# StepperSynth2_4_Interface.net
KiCad netlist of a schematic drawn in EAGLE
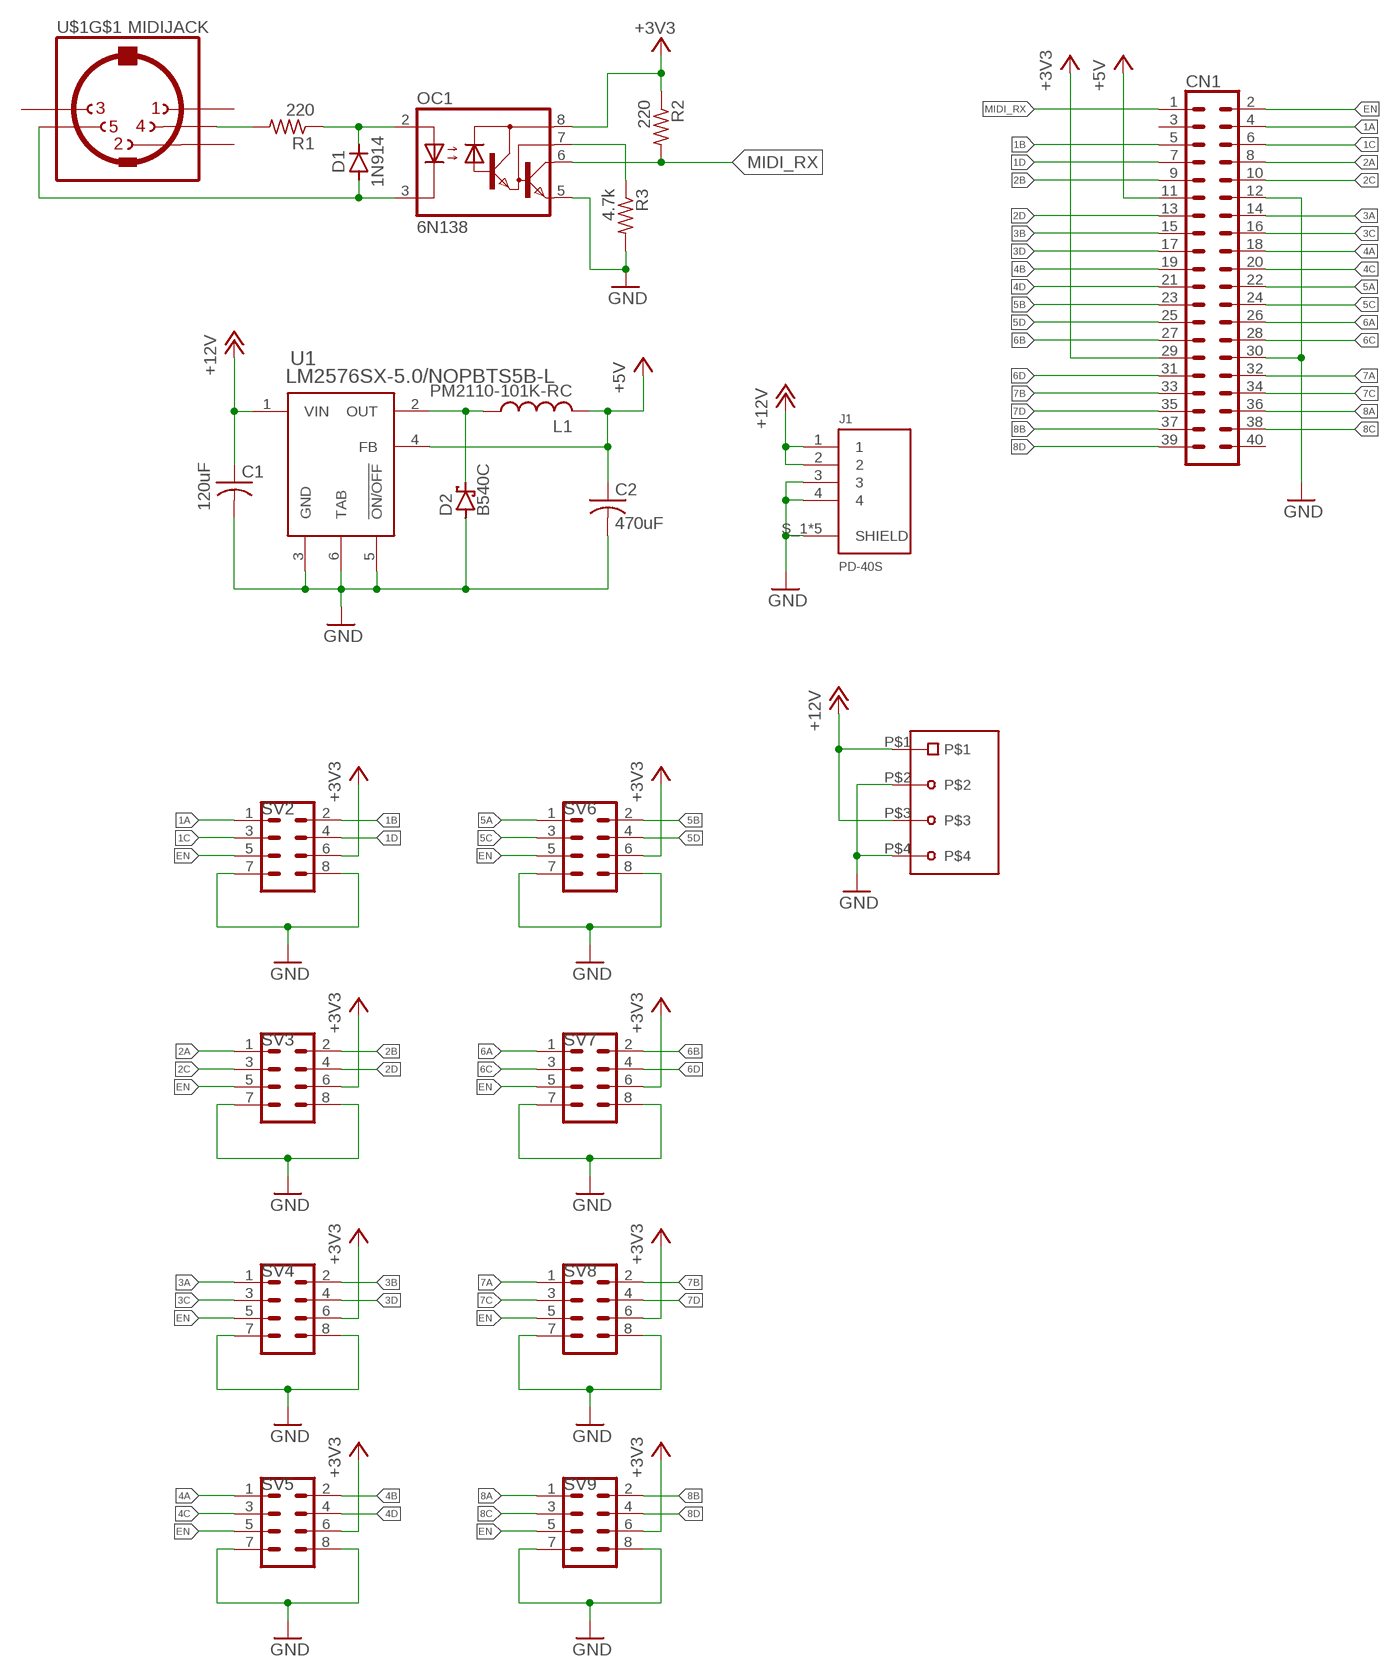
[diagram p0: schematic, sheet 1]

(export (version "E")
  (design (tool "Eeschema 10.0.6"))
  (components
    (comp (ref "C1")
      (value "120uF")
      (footprint "eagle-import:PCAP_SVP_C6-L")
      (fields (field (name "MANUFACTURER_PART_NUMBER") "20SVPF120M"))
      (libsource (lib "eagle-import") (part "20SVPF120MPCAP_SVP_C6-L"))
    )
    (comp (ref "C2")
      (value "470uF")
      (footprint "eagle-import:U2-P-L")
      (fields (field (name "MANUFACTURER_PART_NUMBER") "UUD1A471MNL1GS"))
      (libsource (lib "eagle-import") (part "UUD1A471MNL1GSU2-P-L"))
    )
    (comp (ref "CN1")
      (value "CONN_20X2_LOCK")
      (footprint "eagle-import:1X20_LOCK")
      (libsource (lib "eagle-import") (part "CONN_20X2_LOCK"))
    )
    (comp (ref "CN2")
      (value "SCREW_TERMINAL_4POS_5MM")
      (footprint "eagle-import:4_POS-SCREW_TERM")
      (libsource (lib "eagle-import") (part "SCREW_TERMINAL_4POS_5MM"))
    )
    (comp (ref "D1")
      (value "1N914")
      (footprint "eagle-import:DO35-7")
      (libsource (lib "eagle-import") (part "1N914"))
    )
    (comp (ref "D2")
      (value "B540C")
      (footprint "eagle-import:SMC")
      (libsource (lib "eagle-import") (part "SCHOTTKY-DIODESMC"))
    )
    (comp (ref "J1")
      (value "PD-40S")
      (footprint "eagle-import:CUI_PD-40S")
      (fields (field (name "DIGI-KEY_PART_NUMBER") "CP-7240-ND") (field (name "MF") "CUI Inc."))
      (libsource (lib "eagle-import") (part "PD-40S"))
    )
    (comp (ref "L1")
      (value "PM2110-101K-RC")
      (footprint "eagle-import:IND_PM2110")
      (fields (field (name "MANUFACTURER_PART_NUMBER") "PM2110101KRC"))
      (libsource (lib "eagle-import") (part "PM2110-101K-RC"))
    )
    (comp (ref "OC1")
      (value "6N138")
      (footprint "eagle-import:DIL08")
      (fields (field (name "MF") "VISHAY/TELEFUNKEN"))
      (libsource (lib "eagle-import") (part "6N138"))
    )
    (comp (ref "R1")
      (value "220")
      (footprint "eagle-import:0204_7")
      (libsource (lib "eagle-import") (part "R-US_0204/7"))
    )
    (comp (ref "R2")
      (value "220")
      (footprint "eagle-import:0204_7")
      (libsource (lib "eagle-import") (part "R-US_0204/7"))
    )
    (comp (ref "R3")
      (value "4.7k")
      (footprint "eagle-import:0204_7")
      (libsource (lib "eagle-import") (part "R-US_0204/7"))
    )
    (comp (ref "SV2")
      (value "CONN_4X2_LOCK")
      (footprint "eagle-import:1X04_LOCK")
      (libsource (lib "eagle-import") (part "CONN_4X2_LOCK"))
    )
    (comp (ref "SV3")
      (value "CONN_4X2_LOCK")
      (footprint "eagle-import:1X04_LOCK")
      (libsource (lib "eagle-import") (part "CONN_4X2_LOCK"))
    )
    (comp (ref "SV4")
      (value "CONN_4X2_LOCK")
      (footprint "eagle-import:1X04_LOCK")
      (libsource (lib "eagle-import") (part "CONN_4X2_LOCK"))
    )
    (comp (ref "SV5")
      (value "CONN_4X2_LOCK")
      (footprint "eagle-import:1X04_LOCK")
      (libsource (lib "eagle-import") (part "CONN_4X2_LOCK"))
    )
    (comp (ref "SV6")
      (value "CONN_4X2_LOCK")
      (footprint "eagle-import:1X04_LOCK")
      (libsource (lib "eagle-import") (part "CONN_4X2_LOCK"))
    )
    (comp (ref "SV7")
      (value "CONN_4X2_LOCK")
      (footprint "eagle-import:1X04_LOCK")
      (libsource (lib "eagle-import") (part "CONN_4X2_LOCK"))
    )
    (comp (ref "SV8")
      (value "CONN_4X2_LOCK")
      (footprint "eagle-import:1X04_LOCK")
      (libsource (lib "eagle-import") (part "CONN_4X2_LOCK"))
    )
    (comp (ref "SV9")
      (value "CONN_4X2_LOCK")
      (footprint "eagle-import:1X04_LOCK")
      (libsource (lib "eagle-import") (part "CONN_4X2_LOCK"))
    )
    (comp (ref "U$1")
      (value "MIDIJACK")
      (footprint "eagle-import:CP-2350")
      (libsource (lib "eagle-import") (part "MIDIJACK"))
    )
    (comp (ref "U1")
      (value "LM2576SX-5.0/NOPBTS5B-L")
      (footprint "eagle-import:TS5B-L")
      (fields (field (name "MANUFACTURER_PART_NUMBER") "LM2576SX5.0NOPB"))
      (libsource (lib "eagle-import") (part "LM2576SX-5.0/NOPBTS5B-L"))
    )
  )
  (nets
    (net (code "1") (name "+3V3") (class "Default")
      (node (ref "CN1") (pin "29") (pinfunction "29_29") (pintype "passive"))
      (node (ref "OC1") (pin "8") (pinfunction "VCC_8") (pintype "passive"))
      (node (ref "R2") (pin "1") (pinfunction "1_1") (pintype "passive"))
      (node (ref "SV2") (pin "6") (pinfunction "6_6") (pintype "passive"))
      (node (ref "SV3") (pin "6") (pinfunction "6_6") (pintype "passive"))
      (node (ref "SV4") (pin "6") (pinfunction "6_6") (pintype "passive"))
      (node (ref "SV5") (pin "6") (pinfunction "6_6") (pintype "passive"))
      (node (ref "SV6") (pin "6") (pinfunction "6_6") (pintype "passive"))
      (node (ref "SV7") (pin "6") (pinfunction "6_6") (pintype "passive"))
      (node (ref "SV8") (pin "6") (pinfunction "6_6") (pintype "passive"))
      (node (ref "SV9") (pin "6") (pinfunction "6_6") (pintype "passive"))
    )
    (net (code "2") (name "+5V") (class "Default")
      (node (ref "C2") (pin "1") (pinfunction "+_1") (pintype "passive"))
      (node (ref "CN1") (pin "11") (pinfunction "11_11") (pintype "passive"))
      (node (ref "L1") (pin "2") (pinfunction "2_2") (pintype "passive"))
      (node (ref "U1") (pin "4") (pinfunction "FB_4") (pintype "input"))
    )
    (net (code "3") (name "+12V") (class "Default")
      (node (ref "C1") (pin "1") (pinfunction "+_1") (pintype "passive"))
      (node (ref "CN2") (pin "P$1") (pinfunction "P$1_P$1") (pintype "bidirectional"))
      (node (ref "CN2") (pin "P$3") (pinfunction "P$3_P$3") (pintype "bidirectional"))
      (node (ref "J1") (pin "1") (pinfunction "1_1") (pintype "passive"))
      (node (ref "J1") (pin "2") (pinfunction "2_2") (pintype "passive"))
      (node (ref "U1") (pin "1") (pinfunction "VIN_1") (pintype "power_in"))
    )
    (net (code "4") (name "1A") (class "Default")
      (node (ref "CN1") (pin "4") (pinfunction "4_4") (pintype "passive"))
      (node (ref "SV2") (pin "1") (pinfunction "1_1") (pintype "passive"))
    )
    (net (code "5") (name "1B") (class "Default")
      (node (ref "CN1") (pin "5") (pinfunction "5_5") (pintype "passive"))
      (node (ref "SV2") (pin "2") (pinfunction "2_2") (pintype "passive"))
    )
    (net (code "6") (name "1C") (class "Default")
      (node (ref "CN1") (pin "6") (pinfunction "6_6") (pintype "passive"))
      (node (ref "SV2") (pin "3") (pinfunction "3_3") (pintype "passive"))
    )
    (net (code "7") (name "1D") (class "Default")
      (node (ref "CN1") (pin "7") (pinfunction "7_7") (pintype "passive"))
      (node (ref "SV2") (pin "4") (pinfunction "4_4") (pintype "passive"))
    )
    (net (code "8") (name "2A") (class "Default")
      (node (ref "CN1") (pin "8") (pinfunction "8_8") (pintype "passive"))
      (node (ref "SV3") (pin "1") (pinfunction "1_1") (pintype "passive"))
    )
    (net (code "9") (name "2B") (class "Default")
      (node (ref "CN1") (pin "9") (pinfunction "9_9") (pintype "passive"))
      (node (ref "SV3") (pin "2") (pinfunction "2_2") (pintype "passive"))
    )
    (net (code "10") (name "2C") (class "Default")
      (node (ref "CN1") (pin "10") (pinfunction "10_10") (pintype "passive"))
      (node (ref "SV3") (pin "3") (pinfunction "3_3") (pintype "passive"))
    )
    (net (code "11") (name "2D") (class "Default")
      (node (ref "CN1") (pin "13") (pinfunction "13_13") (pintype "passive"))
      (node (ref "SV3") (pin "4") (pinfunction "4_4") (pintype "passive"))
    )
    (net (code "12") (name "3A") (class "Default")
      (node (ref "CN1") (pin "14") (pinfunction "14_14") (pintype "passive"))
      (node (ref "SV4") (pin "1") (pinfunction "1_1") (pintype "passive"))
    )
    (net (code "13") (name "3B") (class "Default")
      (node (ref "CN1") (pin "15") (pinfunction "15_15") (pintype "passive"))
      (node (ref "SV4") (pin "2") (pinfunction "2_2") (pintype "passive"))
    )
    (net (code "14") (name "3C") (class "Default")
      (node (ref "CN1") (pin "16") (pinfunction "16_16") (pintype "passive"))
      (node (ref "SV4") (pin "3") (pinfunction "3_3") (pintype "passive"))
    )
    (net (code "15") (name "3D") (class "Default")
      (node (ref "CN1") (pin "17") (pinfunction "17_17") (pintype "passive"))
      (node (ref "SV4") (pin "4") (pinfunction "4_4") (pintype "passive"))
    )
    (net (code "16") (name "4A") (class "Default")
      (node (ref "CN1") (pin "18") (pinfunction "18_18") (pintype "passive"))
      (node (ref "SV5") (pin "1") (pinfunction "1_1") (pintype "passive"))
    )
    (net (code "17") (name "4B") (class "Default")
      (node (ref "CN1") (pin "19") (pinfunction "19_19") (pintype "passive"))
      (node (ref "SV5") (pin "2") (pinfunction "2_2") (pintype "passive"))
    )
    (net (code "18") (name "4C") (class "Default")
      (node (ref "CN1") (pin "20") (pinfunction "20_20") (pintype "passive"))
      (node (ref "SV5") (pin "3") (pinfunction "3_3") (pintype "passive"))
    )
    (net (code "19") (name "4D") (class "Default")
      (node (ref "CN1") (pin "21") (pinfunction "21_21") (pintype "passive"))
      (node (ref "SV5") (pin "4") (pinfunction "4_4") (pintype "passive"))
    )
    (net (code "20") (name "5A") (class "Default")
      (node (ref "CN1") (pin "22") (pinfunction "22_22") (pintype "passive"))
      (node (ref "SV6") (pin "1") (pinfunction "1_1") (pintype "passive"))
    )
    (net (code "21") (name "5B") (class "Default")
      (node (ref "CN1") (pin "23") (pinfunction "23_23") (pintype "passive"))
      (node (ref "SV6") (pin "2") (pinfunction "2_2") (pintype "passive"))
    )
    (net (code "22") (name "5C") (class "Default")
      (node (ref "CN1") (pin "24") (pinfunction "24_24") (pintype "passive"))
      (node (ref "SV6") (pin "3") (pinfunction "3_3") (pintype "passive"))
    )
    (net (code "23") (name "5D") (class "Default")
      (node (ref "CN1") (pin "25") (pinfunction "25_25") (pintype "passive"))
      (node (ref "SV6") (pin "4") (pinfunction "4_4") (pintype "passive"))
    )
    (net (code "24") (name "6A") (class "Default")
      (node (ref "CN1") (pin "26") (pinfunction "26_26") (pintype "passive"))
      (node (ref "SV7") (pin "1") (pinfunction "1_1") (pintype "passive"))
    )
    (net (code "25") (name "6B") (class "Default")
      (node (ref "CN1") (pin "27") (pinfunction "27_27") (pintype "passive"))
      (node (ref "SV7") (pin "2") (pinfunction "2_2") (pintype "passive"))
    )
    (net (code "26") (name "6C") (class "Default")
      (node (ref "CN1") (pin "28") (pinfunction "28_28") (pintype "passive"))
      (node (ref "SV7") (pin "3") (pinfunction "3_3") (pintype "passive"))
    )
    (net (code "27") (name "6D") (class "Default")
      (node (ref "CN1") (pin "31") (pinfunction "31_31") (pintype "passive"))
      (node (ref "SV7") (pin "4") (pinfunction "4_4") (pintype "passive"))
    )
    (net (code "28") (name "7A") (class "Default")
      (node (ref "CN1") (pin "32") (pinfunction "32_32") (pintype "passive"))
      (node (ref "SV8") (pin "1") (pinfunction "1_1") (pintype "passive"))
    )
    (net (code "29") (name "7B") (class "Default")
      (node (ref "CN1") (pin "33") (pinfunction "33_33") (pintype "passive"))
      (node (ref "SV8") (pin "2") (pinfunction "2_2") (pintype "passive"))
    )
    (net (code "30") (name "7C") (class "Default")
      (node (ref "CN1") (pin "34") (pinfunction "34_34") (pintype "passive"))
      (node (ref "SV8") (pin "3") (pinfunction "3_3") (pintype "passive"))
    )
    (net (code "31") (name "7D") (class "Default")
      (node (ref "CN1") (pin "35") (pinfunction "35_35") (pintype "passive"))
      (node (ref "SV8") (pin "4") (pinfunction "4_4") (pintype "passive"))
    )
    (net (code "32") (name "8A") (class "Default")
      (node (ref "CN1") (pin "36") (pinfunction "36_36") (pintype "passive"))
      (node (ref "SV9") (pin "1") (pinfunction "1_1") (pintype "passive"))
    )
    (net (code "33") (name "8B") (class "Default")
      (node (ref "CN1") (pin "37") (pinfunction "37_37") (pintype "passive"))
      (node (ref "SV9") (pin "2") (pinfunction "2_2") (pintype "passive"))
    )
    (net (code "34") (name "8C") (class "Default")
      (node (ref "CN1") (pin "38") (pinfunction "38_38") (pintype "passive"))
      (node (ref "SV9") (pin "3") (pinfunction "3_3") (pintype "passive"))
    )
    (net (code "35") (name "8D") (class "Default")
      (node (ref "CN1") (pin "39") (pinfunction "39_39") (pintype "passive"))
      (node (ref "SV9") (pin "4") (pinfunction "4_4") (pintype "passive"))
    )
    (net (code "36") (name "EN") (class "Default")
      (node (ref "CN1") (pin "2") (pinfunction "2_2") (pintype "passive"))
      (node (ref "SV2") (pin "5") (pinfunction "5_5") (pintype "passive"))
      (node (ref "SV3") (pin "5") (pinfunction "5_5") (pintype "passive"))
      (node (ref "SV4") (pin "5") (pinfunction "5_5") (pintype "passive"))
      (node (ref "SV5") (pin "5") (pinfunction "5_5") (pintype "passive"))
      (node (ref "SV6") (pin "5") (pinfunction "5_5") (pintype "passive"))
      (node (ref "SV7") (pin "5") (pinfunction "5_5") (pintype "passive"))
      (node (ref "SV8") (pin "5") (pinfunction "5_5") (pintype "passive"))
      (node (ref "SV9") (pin "5") (pinfunction "5_5") (pintype "passive"))
    )
    (net (code "37") (name "GND") (class "Default")
      (node (ref "C1") (pin "2") (pinfunction "-_2") (pintype "passive"))
      (node (ref "C2") (pin "2") (pinfunction "-_2") (pintype "passive"))
      (node (ref "CN1") (pin "12") (pinfunction "12_12") (pintype "passive"))
      (node (ref "CN1") (pin "30") (pinfunction "30_30") (pintype "passive"))
      (node (ref "CN2") (pin "P$2") (pinfunction "P$2_P$2") (pintype "bidirectional"))
      (node (ref "CN2") (pin "P$4") (pinfunction "P$4_P$4") (pintype "bidirectional"))
      (node (ref "D2") (pin "A") (pinfunction "A_A") (pintype "passive"))
      (node (ref "J1") (pin "3") (pinfunction "3_3") (pintype "passive"))
      (node (ref "J1") (pin "4") (pinfunction "4_4") (pintype "passive"))
      (node (ref "J1") (pin "S_1") (pinfunction "SHIELD_S_1") (pintype "passive"))
      (node (ref "J1") (pin "S_2") (pinfunction "SHIELD_S_2") (pintype "passive"))
      (node (ref "J1") (pin "S_3") (pinfunction "SHIELD_S_3") (pintype "passive"))
      (node (ref "J1") (pin "S_4") (pinfunction "SHIELD_S_4") (pintype "passive"))
      (node (ref "J1") (pin "S_5") (pinfunction "SHIELD_S_5") (pintype "passive"))
      (node (ref "OC1") (pin "5") (pinfunction "GND_5") (pintype "passive"))
      (node (ref "R3") (pin "2") (pinfunction "2_2") (pintype "passive"))
      (node (ref "SV2") (pin "7") (pinfunction "7_7") (pintype "passive"))
      (node (ref "SV2") (pin "8") (pinfunction "8_8") (pintype "passive"))
      (node (ref "SV3") (pin "7") (pinfunction "7_7") (pintype "passive"))
      (node (ref "SV3") (pin "8") (pinfunction "8_8") (pintype "passive"))
      (node (ref "SV4") (pin "7") (pinfunction "7_7") (pintype "passive"))
      (node (ref "SV4") (pin "8") (pinfunction "8_8") (pintype "passive"))
      (node (ref "SV5") (pin "7") (pinfunction "7_7") (pintype "passive"))
      (node (ref "SV5") (pin "8") (pinfunction "8_8") (pintype "passive"))
      (node (ref "SV6") (pin "7") (pinfunction "7_7") (pintype "passive"))
      (node (ref "SV6") (pin "8") (pinfunction "8_8") (pintype "passive"))
      (node (ref "SV7") (pin "7") (pinfunction "7_7") (pintype "passive"))
      (node (ref "SV7") (pin "8") (pinfunction "8_8") (pintype "passive"))
      (node (ref "SV8") (pin "7") (pinfunction "7_7") (pintype "passive"))
      (node (ref "SV8") (pin "8") (pinfunction "8_8") (pintype "passive"))
      (node (ref "SV9") (pin "7") (pinfunction "7_7") (pintype "passive"))
      (node (ref "SV9") (pin "8") (pinfunction "8_8") (pintype "passive"))
      (node (ref "U1") (pin "3") (pinfunction "GND_3") (pintype "power_in"))
      (node (ref "U1") (pin "5") (pinfunction "~{ON/OFF}_5") (pintype "input"))
      (node (ref "U1") (pin "6") (pinfunction "TAB_6") (pintype "power_in"))
    )
    (net (code "38") (name "MIDI_RX") (class "Default")
      (node (ref "CN1") (pin "1") (pinfunction "1_1") (pintype "passive"))
      (node (ref "OC1") (pin "6") (pinfunction "VO_6") (pintype "passive"))
      (node (ref "R2") (pin "2") (pinfunction "2_2") (pintype "passive"))
    )
    (net (code "39") (name "Net-(OC1-A)") (class "Default")
      (node (ref "D1") (pin "C") (pinfunction "C_C") (pintype "passive"))
      (node (ref "OC1") (pin "2") (pinfunction "A_2") (pintype "passive"))
      (node (ref "R1") (pin "1") (pinfunction "1_1") (pintype "passive"))
    )
    (net (code "40") (name "Net-(OC1-C)") (class "Default")
      (node (ref "D1") (pin "A") (pinfunction "A_A") (pintype "passive"))
      (node (ref "OC1") (pin "3") (pinfunction "C_3") (pintype "passive"))
      (node (ref "U$1") (pin "5") (pinfunction "5_5") (pintype "passive"))
    )
    (net (code "41") (name "Net-(OC1-VB)") (class "Default")
      (node (ref "OC1") (pin "7") (pinfunction "VB_7") (pintype "passive"))
      (node (ref "R3") (pin "1") (pinfunction "1_1") (pintype "passive"))
    )
    (net (code "42") (name "Net-(R1-Pad2)") (class "Default")
      (node (ref "R1") (pin "2") (pinfunction "2_2") (pintype "passive"))
      (node (ref "U$1") (pin "4") (pinfunction "4_4") (pintype "passive"))
    )
    (net (code "43") (name "Net-(U1-OUT)") (class "Default")
      (node (ref "D2") (pin "C") (pinfunction "C_C") (pintype "passive"))
      (node (ref "L1") (pin "1") (pinfunction "1_1") (pintype "passive"))
      (node (ref "U1") (pin "2") (pinfunction "OUT_2") (pintype "power_in"))
    )
    (net (code "44") (name "unconnected-(CN1-Pad3)") (class "Default")
      (node (ref "CN1") (pin "3") (pinfunction "3_3") (pintype "passive"))
    )
    (net (code "45") (name "unconnected-(CN1-Pad40)") (class "Default")
      (node (ref "CN1") (pin "40") (pinfunction "40_40") (pintype "passive"))
    )
    (net (code "46") (name "unconnected-(U$1-Pad1)") (class "Default")
      (node (ref "U$1") (pin "1") (pinfunction "1_1") (pintype "passive"))
    )
    (net (code "47") (name "unconnected-(U$1-Pad2)") (class "Default")
      (node (ref "U$1") (pin "2") (pinfunction "2_2") (pintype "passive"))
    )
    (net (code "48") (name "unconnected-(U$1-Pad3)") (class "Default")
      (node (ref "U$1") (pin "3") (pinfunction "3_3") (pintype "passive"))
    )
  )
)
